# SH6_-_High_Side_Driver.net
KiCad netlist of a schematic drawn in Altium Designer
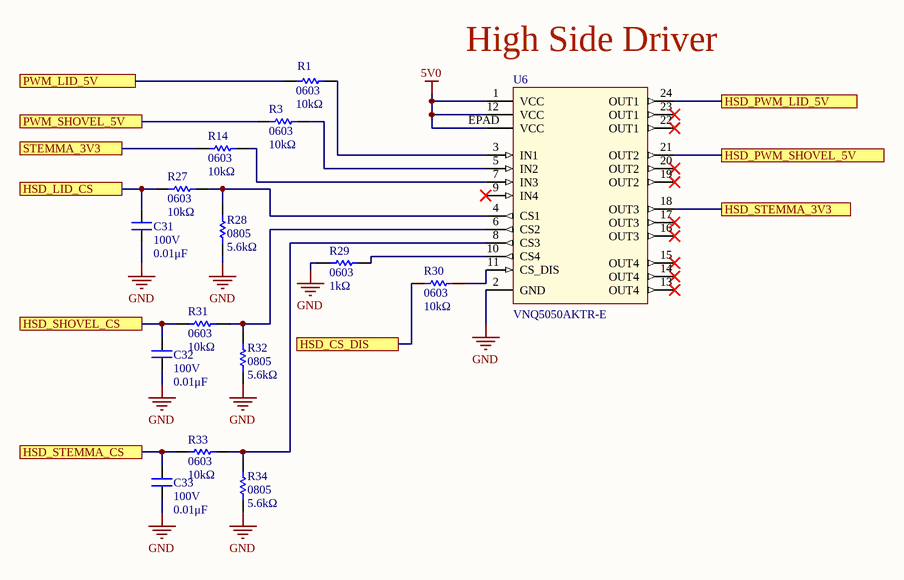
[diagram p0: SH6 - High Side Driver.SchDoc]

(export (version "E")
  (design (tool "Eeschema 10.0.6"))
  (components
    (comp (ref "C31")
      (value "0.01μF")
      (footprint "CAP0603")
      (description "CAP CER 10000PF 100V X7R 0603")
      (fields (field (name "VOLTAGE RATING") "100V") (field (name "Comment") "CAP_0.01uF_100V_0603"))
      (libsource (lib "UWRT_Schematic_Library_2020") (part "CAP_0.01uF_100V_0603"))
    )
    (comp (ref "C32")
      (value "0.01μF")
      (footprint "CAP0603")
      (description "CAP CER 10000PF 100V X7R 0603")
      (fields (field (name "VOLTAGE RATING") "100V") (field (name "Comment") "CAP_0.01uF_100V_0603"))
      (libsource (lib "UWRT_Schematic_Library_2020") (part "CAP_0.01uF_100V_0603"))
    )
    (comp (ref "C33")
      (value "0.01μF")
      (footprint "CAP0603")
      (description "CAP CER 10000PF 100V X7R 0603")
      (fields (field (name "VOLTAGE RATING") "100V") (field (name "Comment") "CAP_0.01uF_100V_0603"))
      (libsource (lib "UWRT_Schematic_Library_2020") (part "CAP_0.01uF_100V_0603"))
    )
    (comp (ref "R1")
      (value "10kΩ")
      (footprint "RESC0603")
      (description "RES 10K OHM 5% 1/10W 0603")
      (fields (field (name "PACKAGE/FOOTPRINT") "0603") (field (name "Comment") "RES_10kΩ_0603_5%"))
      (libsource (lib "UWRT_Schematic_Library_2020") (part "RES_10kΩ_0603_5%"))
    )
    (comp (ref "R3")
      (value "10kΩ")
      (footprint "RESC0603")
      (description "RES 10K OHM 5% 1/10W 0603")
      (fields (field (name "PACKAGE/FOOTPRINT") "0603") (field (name "Comment") "RES_10kΩ_0603_5%"))
      (libsource (lib "UWRT_Schematic_Library_2020") (part "RES_10kΩ_0603_5%"))
    )
    (comp (ref "R14")
      (value "10kΩ")
      (footprint "RESC0603")
      (description "RES 10K OHM 5% 1/10W 0603")
      (fields (field (name "PACKAGE/FOOTPRINT") "0603") (field (name "Comment") "RES_10kΩ_0603_5%"))
      (libsource (lib "UWRT_Schematic_Library_2020") (part "RES_10kΩ_0603_5%"))
    )
    (comp (ref "R27")
      (value "10kΩ")
      (footprint "RESC0603")
      (description "RES 10K OHM 5% 1/10W 0603")
      (fields (field (name "PACKAGE/FOOTPRINT") "0603") (field (name "Comment") "RES_10kΩ_0603_5%"))
      (libsource (lib "UWRT_Schematic_Library_2020") (part "RES_10kΩ_0603_5%"))
    )
    (comp (ref "R28")
      (value "5.6kΩ")
      (footprint "RESC0805")
      (description "RES SMD 5.6K OHM 5% 1/8W 0805")
      (fields
        (field (name "TOLERANCE") "5%")
        (field (name "PACKAGE") "0805")
        (field (name "Comment") "RES_5.6kΩ_0805")
      )
      (libsource (lib "UWRT_Schematic_Library_2020") (part "RES_5.6kΩ_0805_5%"))
    )
    (comp (ref "R29")
      (value "1kΩ")
      (footprint "RESC0603")
      (description "RES 1K OHM 5% 1/10W 0603")
      (fields (field (name "PACKAGE/FOOTPRINT") "0603") (field (name "Comment") "RES_1kΩ_0603_5%"))
      (libsource (lib "UWRT_Schematic_Library_2020") (part "RES_1kΩ_0603_5%"))
    )
    (comp (ref "R30")
      (value "10kΩ")
      (footprint "RESC0603")
      (description "RES 10K OHM 5% 1/10W 0603")
      (fields (field (name "PACKAGE/FOOTPRINT") "0603") (field (name "Comment") "RES_10kΩ_0603_5%"))
      (libsource (lib "UWRT_Schematic_Library_2020") (part "RES_10kΩ_0603_5%"))
    )
    (comp (ref "R31")
      (value "10kΩ")
      (footprint "RESC0603")
      (description "RES 10K OHM 5% 1/10W 0603")
      (fields (field (name "PACKAGE/FOOTPRINT") "0603") (field (name "Comment") "RES_10kΩ_0603_5%"))
      (libsource (lib "UWRT_Schematic_Library_2020") (part "RES_10kΩ_0603_5%"))
    )
    (comp (ref "R32")
      (value "5.6kΩ")
      (footprint "RESC0805")
      (description "RES SMD 5.6K OHM 5% 1/8W 0805")
      (fields
        (field (name "TOLERANCE") "5%")
        (field (name "PACKAGE") "0805")
        (field (name "Comment") "RES_5.6kΩ_0805")
      )
      (libsource (lib "UWRT_Schematic_Library_2020") (part "RES_5.6kΩ_0805_5%"))
    )
    (comp (ref "R33")
      (value "10kΩ")
      (footprint "RESC0603")
      (description "RES 10K OHM 5% 1/10W 0603")
      (fields (field (name "PACKAGE/FOOTPRINT") "0603") (field (name "Comment") "RES_10kΩ_0603_5%"))
      (libsource (lib "UWRT_Schematic_Library_2020") (part "RES_10kΩ_0603_5%"))
    )
    (comp (ref "R34")
      (value "5.6kΩ")
      (footprint "RESC0805")
      (description "RES SMD 5.6K OHM 5% 1/8W 0805")
      (fields
        (field (name "TOLERANCE") "5%")
        (field (name "PACKAGE") "0805")
        (field (name "Comment") "RES_5.6kΩ_0805")
      )
      (libsource (lib "UWRT_Schematic_Library_2020") (part "RES_5.6kΩ_0805_5%"))
    )
    (comp (ref "U6")
      (value "VNQ5050AKTR-E")
      (footprint "PowerSSO-24_STM")
      (description "High Side Driver 24-Pin PowerSSO EP T/R")
      (fields (field (name "MANUFACTURER PART NUMBER 1") "VNQ5050AKTR-E"))
      (libsource (lib "UWRT_Schematic_Library_2020") (part "VNQ5050AKTR-E"))
    )
  )
  (nets
    (net (code "1") (name "/HSD_CS_DIS") (class "Default")
      (node (ref "R30") (pin "1") (pinfunction "1_1") (pintype "passive"))
    )
    (net (code "2") (name "/HSD_LID_CS") (class "Default")
      (node (ref "C31") (pin "2") (pinfunction "2_2") (pintype "passive"))
      (node (ref "R27") (pin "1") (pinfunction "1_1") (pintype "passive"))
    )
    (net (code "3") (name "/HSD_PWM_LID_5V") (class "Default")
      (node (ref "U6") (pin "24") (pinfunction "OUT1_24") (pintype "output"))
    )
    (net (code "4") (name "/HSD_PWM_SHOVEL_5V") (class "Default")
      (node (ref "U6") (pin "21") (pinfunction "OUT2_21") (pintype "output"))
    )
    (net (code "5") (name "/HSD_SHOVEL_CS") (class "Default")
      (node (ref "C32") (pin "2") (pinfunction "2_2") (pintype "passive"))
      (node (ref "R31") (pin "1") (pinfunction "1_1") (pintype "passive"))
    )
    (net (code "6") (name "/HSD_STEMMA_3V3") (class "Default")
      (node (ref "U6") (pin "18") (pinfunction "OUT3_18") (pintype "output"))
    )
    (net (code "7") (name "/HSD_STEMMA_CS") (class "Default")
      (node (ref "C33") (pin "2") (pinfunction "2_2") (pintype "passive"))
      (node (ref "R33") (pin "1") (pinfunction "1_1") (pintype "passive"))
    )
    (net (code "8") (name "/PWM_LID_5V") (class "Default")
      (node (ref "R1") (pin "1") (pinfunction "1_1") (pintype "passive"))
    )
    (net (code "9") (name "/PWM_SHOVEL_5V") (class "Default")
      (node (ref "R3") (pin "1") (pinfunction "1_1") (pintype "passive"))
    )
    (net (code "10") (name "/STEMMA_3V3") (class "Default")
      (node (ref "R14") (pin "1") (pinfunction "1_1") (pintype "passive"))
    )
    (net (code "11") (name "5V0") (class "Default")
      (node (ref "U6") (pin "1") (pinfunction "VCC_1") (pintype "power_in"))
      (node (ref "U6") (pin "12") (pinfunction "VCC_12") (pintype "power_in"))
      (node (ref "U6") (pin "EPAD") (pinfunction "VCC_EPAD") (pintype "power_in"))
    )
    (net (code "12") (name "GND") (class "Default")
      (node (ref "C31") (pin "1") (pinfunction "1_1") (pintype "passive"))
      (node (ref "C32") (pin "1") (pinfunction "1_1") (pintype "passive"))
      (node (ref "C33") (pin "1") (pinfunction "1_1") (pintype "passive"))
      (node (ref "R28") (pin "1") (pinfunction "1_1") (pintype "passive"))
      (node (ref "R29") (pin "1") (pinfunction "1_1") (pintype "passive"))
      (node (ref "R32") (pin "1") (pinfunction "1_1") (pintype "passive"))
      (node (ref "R34") (pin "1") (pinfunction "1_1") (pintype "passive"))
      (node (ref "U6") (pin "2") (pinfunction "GND_2") (pintype "power_in"))
    )
    (net (code "13") (name "Net-(U6-CS1)") (class "Default")
      (node (ref "R27") (pin "2") (pinfunction "2_2") (pintype "passive"))
      (node (ref "R28") (pin "2") (pinfunction "2_2") (pintype "passive"))
      (node (ref "U6") (pin "4") (pinfunction "CS1_4") (pintype "output"))
    )
    (net (code "14") (name "Net-(U6-CS2)") (class "Default")
      (node (ref "R31") (pin "2") (pinfunction "2_2") (pintype "passive"))
      (node (ref "R32") (pin "2") (pinfunction "2_2") (pintype "passive"))
      (node (ref "U6") (pin "6") (pinfunction "CS2_6") (pintype "output"))
    )
    (net (code "15") (name "Net-(U6-CS3)") (class "Default")
      (node (ref "R33") (pin "2") (pinfunction "2_2") (pintype "passive"))
      (node (ref "R34") (pin "2") (pinfunction "2_2") (pintype "passive"))
      (node (ref "U6") (pin "8") (pinfunction "CS3_8") (pintype "output"))
    )
    (net (code "16") (name "Net-(U6-CS4)") (class "Default")
      (node (ref "R29") (pin "2") (pinfunction "2_2") (pintype "passive"))
      (node (ref "U6") (pin "10") (pinfunction "CS4_10") (pintype "output"))
    )
    (net (code "17") (name "Net-(U6-CS_DIS)") (class "Default")
      (node (ref "R30") (pin "2") (pinfunction "2_2") (pintype "passive"))
      (node (ref "U6") (pin "11") (pinfunction "CS_DIS_11") (pintype "input"))
    )
    (net (code "18") (name "Net-(U6-IN1)") (class "Default")
      (node (ref "R1") (pin "2") (pinfunction "2_2") (pintype "passive"))
      (node (ref "U6") (pin "3") (pinfunction "IN1_3") (pintype "input"))
    )
    (net (code "19") (name "Net-(U6-IN2)") (class "Default")
      (node (ref "R3") (pin "2") (pinfunction "2_2") (pintype "passive"))
      (node (ref "U6") (pin "5") (pinfunction "IN2_5") (pintype "input"))
    )
    (net (code "20") (name "Net-(U6-IN3)") (class "Default")
      (node (ref "R14") (pin "2") (pinfunction "2_2") (pintype "passive"))
      (node (ref "U6") (pin "7") (pinfunction "IN3_7") (pintype "input"))
    )
    (net (code "21") (name "unconnected-(U6-IN4-Pad9)") (class "Default")
      (node (ref "U6") (pin "9") (pinfunction "IN4_9") (pintype "input+no_connect"))
    )
    (net (code "22") (name "unconnected-(U6-OUT1-Pad22)") (class "Default")
      (node (ref "U6") (pin "22") (pinfunction "OUT1_22") (pintype "output+no_connect"))
    )
    (net (code "23") (name "unconnected-(U6-OUT1-Pad23)") (class "Default")
      (node (ref "U6") (pin "23") (pinfunction "OUT1_23") (pintype "output+no_connect"))
    )
    (net (code "24") (name "unconnected-(U6-OUT2-Pad19)") (class "Default")
      (node (ref "U6") (pin "19") (pinfunction "OUT2_19") (pintype "output+no_connect"))
    )
    (net (code "25") (name "unconnected-(U6-OUT2-Pad20)") (class "Default")
      (node (ref "U6") (pin "20") (pinfunction "OUT2_20") (pintype "output+no_connect"))
    )
    (net (code "26") (name "unconnected-(U6-OUT3-Pad16)") (class "Default")
      (node (ref "U6") (pin "16") (pinfunction "OUT3_16") (pintype "output+no_connect"))
    )
    (net (code "27") (name "unconnected-(U6-OUT3-Pad17)") (class "Default")
      (node (ref "U6") (pin "17") (pinfunction "OUT3_17") (pintype "output+no_connect"))
    )
    (net (code "28") (name "unconnected-(U6-OUT4-Pad13)") (class "Default")
      (node (ref "U6") (pin "13") (pinfunction "OUT4_13") (pintype "output+no_connect"))
    )
    (net (code "29") (name "unconnected-(U6-OUT4-Pad14)") (class "Default")
      (node (ref "U6") (pin "14") (pinfunction "OUT4_14") (pintype "output+no_connect"))
    )
    (net (code "30") (name "unconnected-(U6-OUT4-Pad15)") (class "Default")
      (node (ref "U6") (pin "15") (pinfunction "OUT4_15") (pintype "output+no_connect"))
    )
  )
)
